# Mounting_Holes.net
KiCad netlist of a schematic drawn in Altium Designer
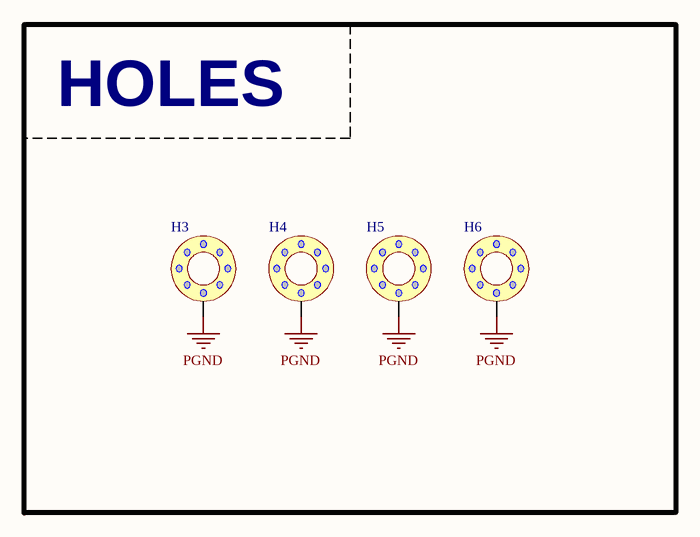
[diagram p0: Mounting Holes.SchDoc]

(export (version "E")
  (design (tool "Eeschema 10.0.6"))
  (components
    (comp (ref "H3")
      (value "Shield")
      (footprint "HEX-M3")
      (libsource (lib "KIENASIY123_LIB") (part "Shield"))
    )
    (comp (ref "H4")
      (value "Shield")
      (footprint "HEX-M3")
      (libsource (lib "KIENASIY123_LIB") (part "Shield"))
    )
    (comp (ref "H5")
      (value "Shield")
      (footprint "HEX-M3")
      (libsource (lib "KIENASIY123_LIB") (part "Shield"))
    )
    (comp (ref "H6")
      (value "Shield")
      (footprint "HEX-M3")
      (libsource (lib "KIENASIY123_LIB") (part "Shield"))
    )
  )
  (nets
    (net (code "1") (name "PGND") (class "Default")
      (node (ref "H3") (pin "1") (pinfunction "1_1") (pintype "passive"))
      (node (ref "H4") (pin "1") (pinfunction "1_1") (pintype "passive"))
      (node (ref "H5") (pin "1") (pinfunction "1_1") (pintype "passive"))
      (node (ref "H6") (pin "1") (pinfunction "1_1") (pintype "passive"))
    )
  )
)
